# 11_SERIAL_PORT.net
KiCad netlist of a schematic drawn in Altium Designer
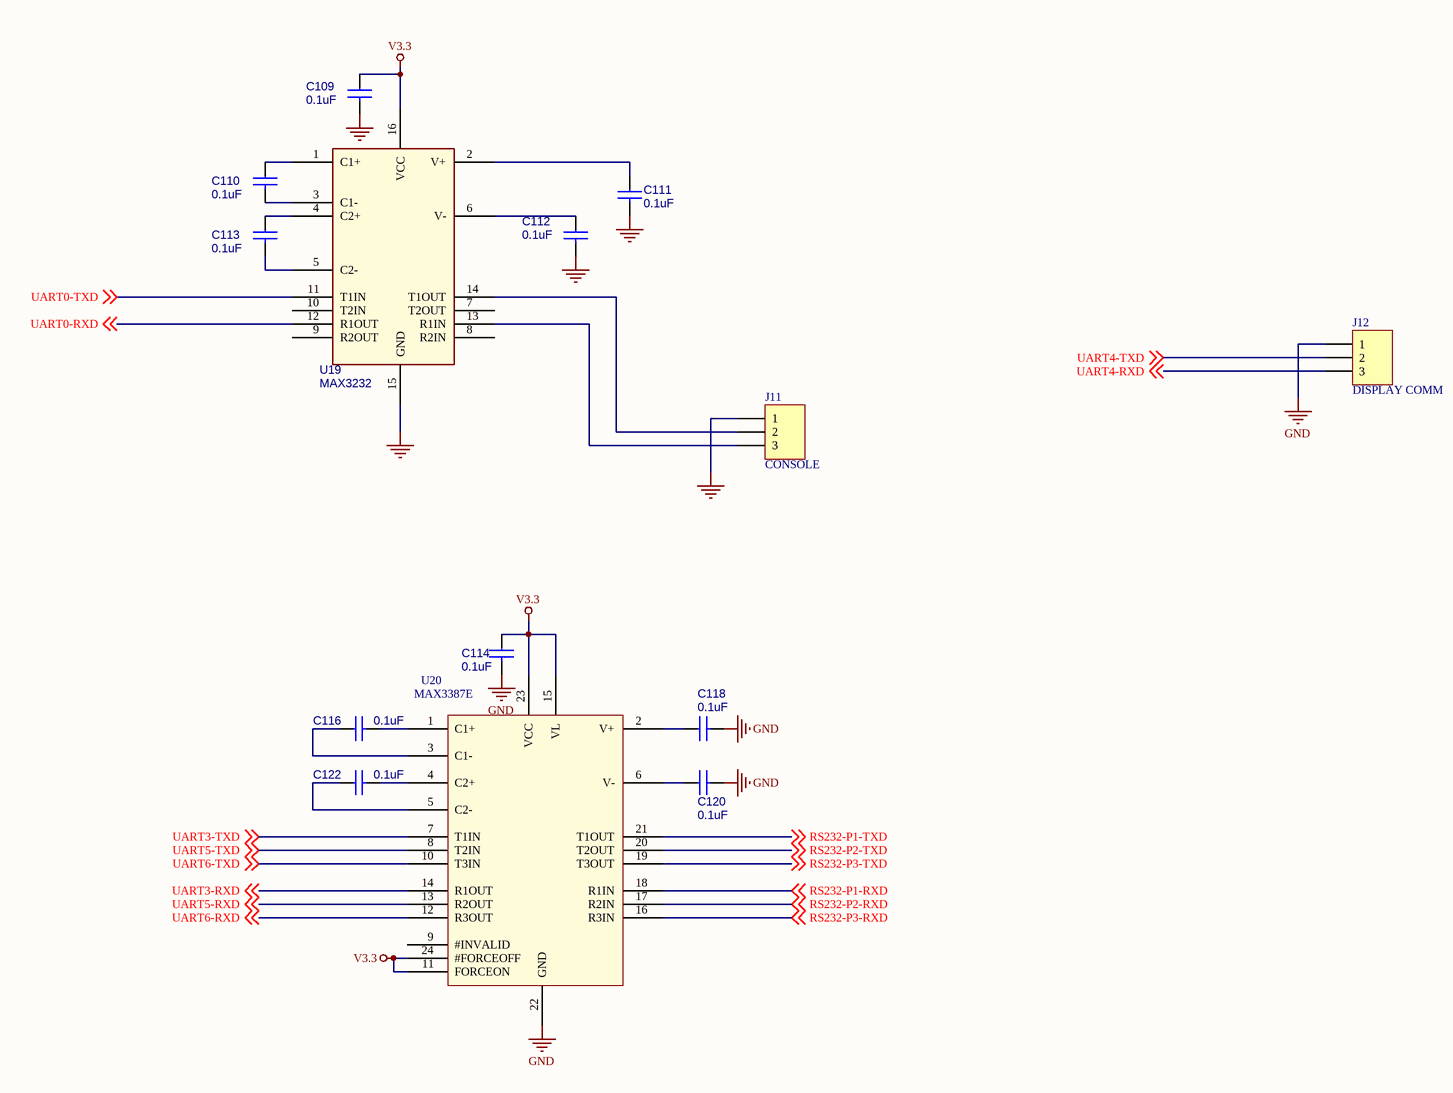
[diagram p0: [11]SERIAL_PORT.SchDoc]

(export (version "E")
  (design (tool "Eeschema 10.0.6"))
  (components
    (comp (ref "C109") (value "0.1uF") (libsource (lib "*") (part "CAP")))
    (comp (ref "C110") (value "0.1uF") (libsource (lib "*") (part "CAP")))
    (comp (ref "C111") (value "0.1uF") (libsource (lib "*") (part "CAP")))
    (comp (ref "C112") (value "0.1uF") (libsource (lib "*") (part "CAP")))
    (comp (ref "C113") (value "0.1uF") (libsource (lib "*") (part "CAP")))
    (comp (ref "C114") (value "0.1uF") (libsource (lib "*") (part "CAP")))
    (comp (ref "C116") (value "0.1uF") (libsource (lib "*") (part "CAP")))
    (comp (ref "C118") (value "0.1uF") (libsource (lib "*") (part "CAP")))
    (comp (ref "C120") (value "0.1uF") (libsource (lib "*") (part "CAP")))
    (comp (ref "C122") (value "0.1uF") (libsource (lib "*") (part "CAP")))
    (comp (ref "J11")
      (value "CONSOLE")
      (footprint "CONN-3P")
      (description "Header, 3-Pin")
      (fields (field (name "PUBLISHER") "Altium Limited"))
      (libsource (lib "Miscellaneous Connectors") (part "Header 3"))
    )
    (comp (ref "J12")
      (value "DISPLAY COMM")
      (footprint "CONN-3P")
      (description "Header, 3-Pin")
      (fields (field (name "PUBLISHER") "Altium Limited"))
      (libsource (lib "Miscellaneous Connectors") (part "Header 3"))
    )
    (comp (ref "U19") (value "MAX3232") (footprint "SO-16") (libsource (lib "*") (part "MAX3232")))
    (comp (ref "U20") (value "MAX3387E") (footprint "SSOP24") (libsource (lib "Schlib") (part "MAX3387E")))
  )
  (nets
    (net (code "1") (name "GND") (class "Default")
      (node (ref "C109") (pin "2") (pinfunction "2_2") (pintype "passive"))
      (node (ref "C111") (pin "2") (pinfunction "2_2") (pintype "passive"))
      (node (ref "C112") (pin "2") (pinfunction "2_2") (pintype "passive"))
      (node (ref "C114") (pin "2") (pinfunction "2_2") (pintype "passive"))
      (node (ref "C118") (pin "2") (pinfunction "2_2") (pintype "passive"))
      (node (ref "C120") (pin "2") (pinfunction "2_2") (pintype "passive"))
      (node (ref "J11") (pin "1") (pinfunction "1_1") (pintype "passive"))
      (node (ref "J12") (pin "1") (pinfunction "1_1") (pintype "passive"))
      (node (ref "U19") (pin "15") (pinfunction "GND_15") (pintype "passive"))
      (node (ref "U20") (pin "22") (pinfunction "GND_22") (pintype "passive"))
    )
    (net (code "2") (name "Net-(U19-C1+)") (class "Default")
      (node (ref "C110") (pin "1") (pinfunction "1_1") (pintype "passive"))
      (node (ref "U19") (pin "1") (pinfunction "C1+_1") (pintype "passive"))
    )
    (net (code "3") (name "Net-(U19-C1-)") (class "Default")
      (node (ref "C110") (pin "2") (pinfunction "2_2") (pintype "passive"))
      (node (ref "U19") (pin "3") (pinfunction "C1-_3") (pintype "passive"))
    )
    (net (code "4") (name "Net-(U19-C2+)") (class "Default")
      (node (ref "C113") (pin "1") (pinfunction "1_1") (pintype "passive"))
      (node (ref "U19") (pin "4") (pinfunction "C2+_4") (pintype "passive"))
    )
    (net (code "5") (name "Net-(U19-C2-)") (class "Default")
      (node (ref "C113") (pin "2") (pinfunction "2_2") (pintype "passive"))
      (node (ref "U19") (pin "5") (pinfunction "C2-_5") (pintype "passive"))
    )
    (net (code "6") (name "Net-(U19-R1IN)") (class "Default")
      (node (ref "J11") (pin "3") (pinfunction "3_3") (pintype "passive"))
      (node (ref "U19") (pin "13") (pinfunction "R1IN_13") (pintype "passive"))
    )
    (net (code "7") (name "Net-(U19-T1OUT)") (class "Default")
      (node (ref "J11") (pin "2") (pinfunction "2_2") (pintype "passive"))
      (node (ref "U19") (pin "14") (pinfunction "T1OUT_14") (pintype "passive"))
    )
    (net (code "8") (name "Net-(U19-V+)") (class "Default")
      (node (ref "C111") (pin "1") (pinfunction "1_1") (pintype "passive"))
      (node (ref "U19") (pin "2") (pinfunction "V+_2") (pintype "passive"))
    )
    (net (code "9") (name "Net-(U19-V-)") (class "Default")
      (node (ref "C112") (pin "1") (pinfunction "1_1") (pintype "passive"))
      (node (ref "U19") (pin "6") (pinfunction "V-_6") (pintype "passive"))
    )
    (net (code "10") (name "Net-(U20-C1+)") (class "Default")
      (node (ref "C116") (pin "2") (pinfunction "2_2") (pintype "passive"))
      (node (ref "U20") (pin "1") (pinfunction "C1+_1") (pintype "passive"))
    )
    (net (code "11") (name "Net-(U20-C1-)") (class "Default")
      (node (ref "C116") (pin "1") (pinfunction "1_1") (pintype "passive"))
      (node (ref "U20") (pin "3") (pinfunction "C1-_3") (pintype "passive"))
    )
    (net (code "12") (name "Net-(U20-C2+)") (class "Default")
      (node (ref "C122") (pin "2") (pinfunction "2_2") (pintype "passive"))
      (node (ref "U20") (pin "4") (pinfunction "C2+_4") (pintype "passive"))
    )
    (net (code "13") (name "Net-(U20-C2-)") (class "Default")
      (node (ref "C122") (pin "1") (pinfunction "1_1") (pintype "passive"))
      (node (ref "U20") (pin "5") (pinfunction "C2-_5") (pintype "passive"))
    )
    (net (code "14") (name "Net-(U20-V+)") (class "Default")
      (node (ref "C118") (pin "1") (pinfunction "1_1") (pintype "passive"))
      (node (ref "U20") (pin "2") (pinfunction "V+_2") (pintype "passive"))
    )
    (net (code "15") (name "Net-(U20-V-)") (class "Default")
      (node (ref "C120") (pin "1") (pinfunction "1_1") (pintype "passive"))
      (node (ref "U20") (pin "6") (pinfunction "V-_6") (pintype "passive"))
    )
    (net (code "16") (name "RS232-P1-RXD") (class "Default")
      (node (ref "U20") (pin "18") (pinfunction "R1IN_18") (pintype "passive"))
    )
    (net (code "17") (name "RS232-P1-TXD") (class "Default")
      (node (ref "U20") (pin "21") (pinfunction "T1OUT_21") (pintype "passive"))
    )
    (net (code "18") (name "RS232-P2-RXD") (class "Default")
      (node (ref "U20") (pin "17") (pinfunction "R2IN_17") (pintype "passive"))
    )
    (net (code "19") (name "RS232-P2-TXD") (class "Default")
      (node (ref "U20") (pin "20") (pinfunction "T2OUT_20") (pintype "passive"))
    )
    (net (code "20") (name "RS232-P3-RXD") (class "Default")
      (node (ref "U20") (pin "16") (pinfunction "R3IN_16") (pintype "passive"))
    )
    (net (code "21") (name "RS232-P3-TXD") (class "Default")
      (node (ref "U20") (pin "19") (pinfunction "T3OUT_19") (pintype "passive"))
    )
    (net (code "22") (name "UART0-RXD") (class "Default")
      (node (ref "U19") (pin "12") (pinfunction "R1OUT_12") (pintype "passive"))
    )
    (net (code "23") (name "UART0-TXD") (class "Default")
      (node (ref "U19") (pin "11") (pinfunction "T1IN_11") (pintype "passive"))
    )
    (net (code "24") (name "UART3-RXD") (class "Default")
      (node (ref "U20") (pin "14") (pinfunction "R1OUT_14") (pintype "passive"))
    )
    (net (code "25") (name "UART3-TXD") (class "Default")
      (node (ref "U20") (pin "7") (pinfunction "T1IN_7") (pintype "passive"))
    )
    (net (code "26") (name "UART4-RXD") (class "Default")
      (node (ref "J12") (pin "3") (pinfunction "3_3") (pintype "passive"))
    )
    (net (code "27") (name "UART4-TXD") (class "Default")
      (node (ref "J12") (pin "2") (pinfunction "2_2") (pintype "passive"))
    )
    (net (code "28") (name "UART5-RXD") (class "Default")
      (node (ref "U20") (pin "13") (pinfunction "R2OUT_13") (pintype "passive"))
    )
    (net (code "29") (name "UART5-TXD") (class "Default")
      (node (ref "U20") (pin "8") (pinfunction "T2IN_8") (pintype "passive"))
    )
    (net (code "30") (name "UART6-RXD") (class "Default")
      (node (ref "U20") (pin "12") (pinfunction "R3OUT_12") (pintype "passive"))
    )
    (net (code "31") (name "UART6-TXD") (class "Default")
      (node (ref "U20") (pin "10") (pinfunction "T3IN_10") (pintype "passive"))
    )
    (net (code "32") (name "V3.3") (class "Default")
      (node (ref "C109") (pin "1") (pinfunction "1_1") (pintype "passive"))
      (node (ref "C114") (pin "1") (pinfunction "1_1") (pintype "passive"))
      (node (ref "U19") (pin "16") (pinfunction "VCC_16") (pintype "passive"))
      (node (ref "U20") (pin "11") (pinfunction "FORCEON_11") (pintype "passive"))
      (node (ref "U20") (pin "15") (pinfunction "VL_15") (pintype "passive"))
      (node (ref "U20") (pin "23") (pinfunction "VCC_23") (pintype "passive"))
      (node (ref "U20") (pin "24") (pinfunction "#FORCEOFF_24") (pintype "passive"))
    )
    (net (code "33") (name "unconnected-(U19-R2IN-Pad8)") (class "Default")
      (node (ref "U19") (pin "8") (pinfunction "R2IN_8") (pintype "passive"))
    )
    (net (code "34") (name "unconnected-(U19-R2OUT-Pad9)") (class "Default")
      (node (ref "U19") (pin "9") (pinfunction "R2OUT_9") (pintype "passive"))
    )
    (net (code "35") (name "unconnected-(U19-T2IN-Pad10)") (class "Default")
      (node (ref "U19") (pin "10") (pinfunction "T2IN_10") (pintype "passive"))
    )
    (net (code "36") (name "unconnected-(U19-T2OUT-Pad7)") (class "Default")
      (node (ref "U19") (pin "7") (pinfunction "T2OUT_7") (pintype "passive"))
    )
    (net (code "37") (name "unconnected-(U20-#INVALID-Pad9)") (class "Default")
      (node (ref "U20") (pin "9") (pinfunction "#INVALID_9") (pintype "passive"))
    )
  )
)
